# Rocket-Control5.net
KiCad netlist of a schematic drawn in EAGLE
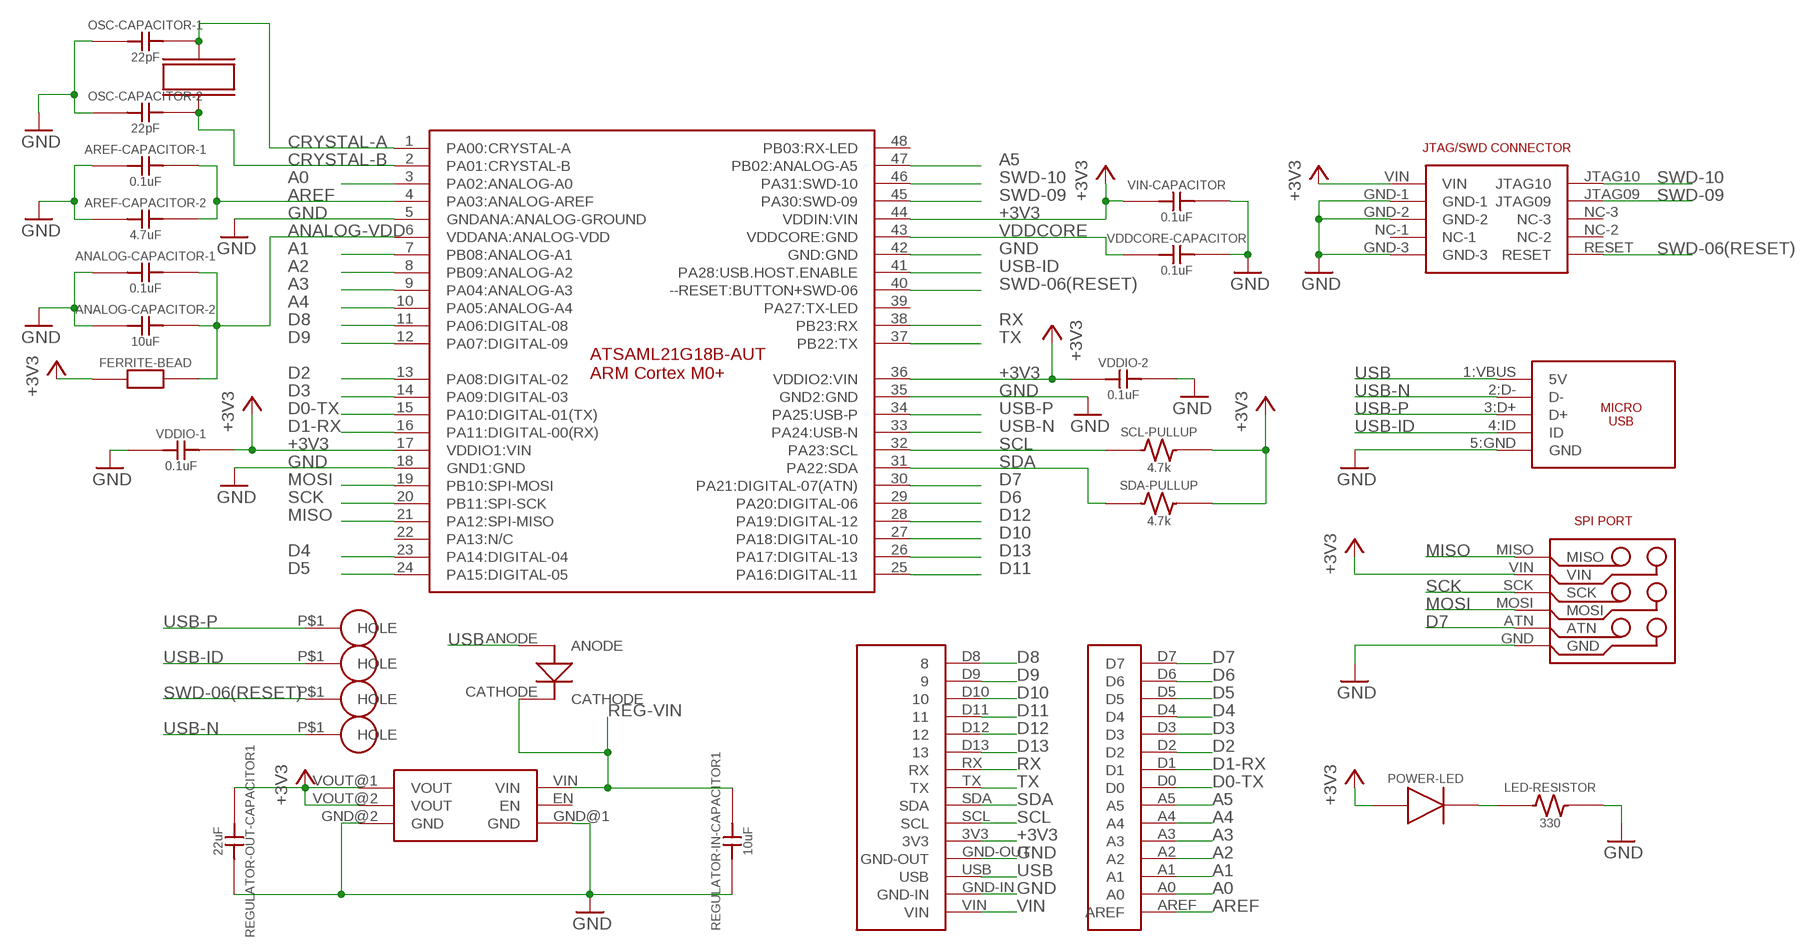
[diagram p0: schematic, sheet 1]

(export (version "E")
  (design (tool "Eeschema 10.0.6"))
  (components
    (comp (ref "ANALOG-CAPACITOR-1")
      (value "0.1uF")
      (footprint "eagle-import:C0402")
      (fields (field (name "MANF") "Samsung Electro-Mechanics America, Inc."))
      (libsource (lib "eagle-import") (part "CAPACITORC0402"))
    )
    (comp (ref "ANALOG-CAPACITOR-2")
      (value "10uF")
      (footprint "eagle-import:C0402")
      (fields (field (name "MANF") "Samsung Electro-Mechanics America, Inc."))
      (libsource (lib "eagle-import") (part "CAPACITORC0402"))
    )
    (comp (ref "AREF-CAPACITOR-1")
      (value "0.1uF")
      (footprint "eagle-import:C0402")
      (fields (field (name "MANF") "Samsung Electro-Mechanics America, Inc."))
      (libsource (lib "eagle-import") (part "CAPACITORC0402"))
    )
    (comp (ref "AREF-CAPACITOR-2")
      (value "4.7uF")
      (footprint "eagle-import:C0402")
      (fields (field (name "MANF") "Samsung Electro-Mechanics America, Inc."))
      (libsource (lib "eagle-import") (part "CAPACITORC0402"))
    )
    (comp (ref "ARM-CORTEX-MO+")
      (value "ATSAML21G18B-AUT")
      (footprint "eagle-import:TQFP48")
      (fields (field (name "MANF") "Microchip Technology"))
      (libsource (lib "eagle-import") (part "ATSAML21G18B-AUT"))
    )
    (comp (ref "FERRITE-BEAD")
      (value "BLM18PG471SN1D")
      (footprint "eagle-import:C0603")
      (fields (field (name "MANF") "Murata Electronics North America"))
      (libsource (lib "eagle-import") (part "BLM18PG471SN1D"))
    )
    (comp (ref "HEADER-SIDE-A")
      (value "HEADER-SIDE-A")
      (footprint "eagle-import:HEADER-SIDE-A")
      (libsource (lib "eagle-import") (part "HEADER-SIDE-A"))
    )
    (comp (ref "HEADER-SIDE-B")
      (value "HEADER-SIDE-B")
      (footprint "eagle-import:HEADER-SIDE-B")
      (fields (field (name "MANF") "Sullins Connector Solutions"))
      (libsource (lib "eagle-import") (part "HEADER-SIDE-B"))
    )
    (comp (ref "JTAG-CONNECTOR")
      (value "JTAG-MINI")
      (footprint "eagle-import:JTAG-MINI")
      (fields (field (name "MANF") "Amphenol FCI"))
      (libsource (lib "eagle-import") (part "JTAG-MINI"))
    )
    (comp (ref "LED-RESISTOR")
      (value "330")
      (footprint "eagle-import:C0603")
      (fields (field (name "MANF") "Samsung Electro-Mechanics America, Inc."))
      (libsource (lib "eagle-import") (part "RESISTORC0603"))
    )
    (comp (ref "MICRO-USB-CONNECTOR")
      (value "10118194-0001LF")
      (footprint "eagle-import:10118194-0001LF")
      (fields (field (name "MANF") "Amphenol FCI"))
      (libsource (lib "eagle-import") (part "10118194-0001LF"))
    )
    (comp (ref "OSC-CAPACITOR-1")
      (value "22pF")
      (footprint "eagle-import:C0603")
      (fields (field (name "MANF") "Samsung Electro-Mechanics America, Inc."))
      (libsource (lib "eagle-import") (part "CAPACITORC0603"))
    )
    (comp (ref "OSC-CAPACITOR-2")
      (value "22pF")
      (footprint "eagle-import:C0603")
      (fields (field (name "MANF") "Samsung Electro-Mechanics America, Inc."))
      (libsource (lib "eagle-import") (part "CAPACITORC0603"))
    )
    (comp (ref "POWER-LED")
      (value "APTD1608ZGC")
      (footprint "eagle-import:C0603")
      (fields (field (name "MANF") "Kingbright"))
      (libsource (lib "eagle-import") (part "APTD1608ZGC"))
    )
    (comp (ref "REGULATOR-IN-CAPACITOR1")
      (value "10uF")
      (footprint "eagle-import:C0402")
      (fields (field (name "MANF") "Samsung Electro-Mechanics America, Inc."))
      (libsource (lib "eagle-import") (part "CAPACITORC0402"))
    )
    (comp (ref "REGULATOR-OUT-CAPACITOR1")
      (value "22uF")
      (footprint "eagle-import:C0402")
      (fields (field (name "MANF") "Samsung Electro-Mechanics America, Inc."))
      (libsource (lib "eagle-import") (part "CAPACITORC0402"))
    )
    (comp (ref "SCL-PULLUP")
      (value "4.7k")
      (footprint "eagle-import:C0402")
      (fields (field (name "MANF") "Samsung Electro-Mechanics America, Inc."))
      (libsource (lib "eagle-import") (part "RESISTORC0402"))
    )
    (comp (ref "SDA-PULLUP")
      (value "4.7k")
      (footprint "eagle-import:C0402")
      (fields (field (name "MANF") "Samsung Electro-Mechanics America, Inc."))
      (libsource (lib "eagle-import") (part "RESISTORC0402"))
    )
    (comp (ref "SPI-PORT")
      (value "SPI-PORT")
      (footprint "eagle-import:SPI-PORT")
      (libsource (lib "eagle-import") (part "SPI-PORT"))
    )
    (comp (ref "U$1")
      (value "ABS07-32.768KHZ-T")
      (footprint "eagle-import:ABS07-32.768KHZ-T")
      (fields (field (name "MANF") "Abracon LLC"))
      (libsource (lib "eagle-import") (part "ABS07-32.768KHZ-T"))
    )
    (comp (ref "U$2")
      (value "MIC5528")
      (footprint "eagle-import:MIC5528")
      (fields (field (name "MANF") "Microchip Technology"))
      (libsource (lib "eagle-import") (part "MIC5528"))
    )
    (comp (ref "U$3")
      (value "DIODE-STANDARD")
      (footprint "eagle-import:DIODE-STANDARD")
      (fields (field (name "MANF") "Panasonic Electronic Components"))
      (libsource (lib "eagle-import") (part "DIODE-STANDARD"))
    )
    (comp (ref "U$4")
      (value "HEADER-HOLE")
      (footprint "eagle-import:HEADER-HOLE")
      (libsource (lib "eagle-import") (part "HEADER-HOLE"))
    )
    (comp (ref "U$5")
      (value "HEADER-HOLE")
      (footprint "eagle-import:HEADER-HOLE")
      (libsource (lib "eagle-import") (part "HEADER-HOLE"))
    )
    (comp (ref "U$6")
      (value "HEADER-HOLE")
      (footprint "eagle-import:HEADER-HOLE")
      (libsource (lib "eagle-import") (part "HEADER-HOLE"))
    )
    (comp (ref "U$7")
      (value "HEADER-HOLE")
      (footprint "eagle-import:HEADER-HOLE")
      (libsource (lib "eagle-import") (part "HEADER-HOLE"))
    )
    (comp (ref "VDDCORE-CAPACITOR")
      (value "0.1uF")
      (footprint "eagle-import:C0402")
      (fields (field (name "MANF") "Samsung Electro-Mechanics America, Inc."))
      (libsource (lib "eagle-import") (part "CAPACITORC0402"))
    )
    (comp (ref "VDDIO-1")
      (value "0.1uF")
      (footprint "eagle-import:C0402")
      (fields (field (name "MANF") "Samsung Electro-Mechanics America, Inc."))
      (libsource (lib "eagle-import") (part "CAPACITORC0402"))
    )
    (comp (ref "VDDIO-2")
      (value "0.1uF")
      (footprint "eagle-import:C0402")
      (fields (field (name "MANF") "Samsung Electro-Mechanics America, Inc."))
      (libsource (lib "eagle-import") (part "CAPACITORC0402"))
    )
    (comp (ref "VIN-CAPACITOR")
      (value "0.1uF")
      (footprint "eagle-import:C0402")
      (fields (field (name "MANF") "Samsung Electro-Mechanics America, Inc."))
      (libsource (lib "eagle-import") (part "CAPACITORC0402"))
    )
  )
  (nets
    (net (code "1") (name "+3V3") (class "Default")
      (node (ref "ARM-CORTEX-MO+") (pin "17") (pinfunction "VDDIO1:VIN_17") (pintype "bidirectional"))
      (node (ref "ARM-CORTEX-MO+") (pin "36") (pinfunction "VDDIO2:VIN_36") (pintype "bidirectional"))
      (node (ref "ARM-CORTEX-MO+") (pin "44") (pinfunction "VDDIN:VIN_44") (pintype "bidirectional"))
      (node (ref "FERRITE-BEAD") (pin "1") (pinfunction "P$1_1") (pintype "bidirectional"))
      (node (ref "HEADER-SIDE-B") (pin "3V3") (pinfunction "3V3_3V3") (pintype "bidirectional"))
      (node (ref "JTAG-CONNECTOR") (pin "VIN") (pinfunction "VIN_VIN") (pintype "bidirectional"))
      (node (ref "POWER-LED") (pin "1") (pinfunction "P$1_1") (pintype "bidirectional"))
      (node (ref "REGULATOR-OUT-CAPACITOR1") (pin "1") (pinfunction "A_1") (pintype "bidirectional"))
      (node (ref "SCL-PULLUP") (pin "2") (pinfunction "P$2_2") (pintype "bidirectional"))
      (node (ref "SDA-PULLUP") (pin "2") (pinfunction "P$2_2") (pintype "bidirectional"))
      (node (ref "SPI-PORT") (pin "VIN") (pinfunction "VIN_VIN") (pintype "bidirectional"))
      (node (ref "U$2") (pin "VOUT@1") (pinfunction "VOUT_VOUT@1") (pintype "bidirectional"))
      (node (ref "U$2") (pin "VOUT@2") (pinfunction "VOUT_VOUT@2") (pintype "bidirectional"))
      (node (ref "VDDIO-1") (pin "2") (pinfunction "B_2") (pintype "bidirectional"))
      (node (ref "VDDIO-2") (pin "2") (pinfunction "B_2") (pintype "bidirectional"))
      (node (ref "VIN-CAPACITOR") (pin "1") (pinfunction "A_1") (pintype "bidirectional"))
    )
    (net (code "2") (name "/A0") (class "Default")
      (node (ref "ARM-CORTEX-MO+") (pin "3") (pinfunction "PA02:ANALOG-A0_3") (pintype "bidirectional"))
      (node (ref "HEADER-SIDE-A") (pin "A0") (pinfunction "A0_A0") (pintype "bidirectional"))
    )
    (net (code "3") (name "/A1") (class "Default")
      (node (ref "ARM-CORTEX-MO+") (pin "7") (pinfunction "PB08:ANALOG-A1_7") (pintype "bidirectional"))
      (node (ref "HEADER-SIDE-A") (pin "A1") (pinfunction "A1_A1") (pintype "bidirectional"))
    )
    (net (code "4") (name "/A2") (class "Default")
      (node (ref "ARM-CORTEX-MO+") (pin "8") (pinfunction "PB09:ANALOG-A2_8") (pintype "bidirectional"))
      (node (ref "HEADER-SIDE-A") (pin "A2") (pinfunction "A2_A2") (pintype "bidirectional"))
    )
    (net (code "5") (name "/A3") (class "Default")
      (node (ref "ARM-CORTEX-MO+") (pin "9") (pinfunction "PA04:ANALOG-A3_9") (pintype "bidirectional"))
      (node (ref "HEADER-SIDE-A") (pin "A3") (pinfunction "A3_A3") (pintype "bidirectional"))
    )
    (net (code "6") (name "/A4") (class "Default")
      (node (ref "ARM-CORTEX-MO+") (pin "10") (pinfunction "PA05:ANALOG-A4_10") (pintype "bidirectional"))
      (node (ref "HEADER-SIDE-A") (pin "A4") (pinfunction "A4_A4") (pintype "bidirectional"))
    )
    (net (code "7") (name "/A5") (class "Default")
      (node (ref "ARM-CORTEX-MO+") (pin "47") (pinfunction "PB02:ANALOG-A5_47") (pintype "bidirectional"))
      (node (ref "HEADER-SIDE-A") (pin "A5") (pinfunction "A5_A5") (pintype "bidirectional"))
    )
    (net (code "8") (name "/ANALOG-VDD") (class "Default")
      (node (ref "ANALOG-CAPACITOR-1") (pin "2") (pinfunction "B_2") (pintype "bidirectional"))
      (node (ref "ANALOG-CAPACITOR-2") (pin "2") (pinfunction "B_2") (pintype "bidirectional"))
      (node (ref "ARM-CORTEX-MO+") (pin "6") (pinfunction "VDDANA:ANALOG-VDD_6") (pintype "bidirectional"))
      (node (ref "FERRITE-BEAD") (pin "2") (pinfunction "P$2_2") (pintype "bidirectional"))
    )
    (net (code "9") (name "/AREF") (class "Default")
      (node (ref "AREF-CAPACITOR-1") (pin "2") (pinfunction "B_2") (pintype "bidirectional"))
      (node (ref "AREF-CAPACITOR-2") (pin "2") (pinfunction "B_2") (pintype "bidirectional"))
      (node (ref "ARM-CORTEX-MO+") (pin "4") (pinfunction "PA03:ANALOG-AREF_4") (pintype "bidirectional"))
      (node (ref "HEADER-SIDE-A") (pin "AREF") (pinfunction "AREF_AREF") (pintype "bidirectional"))
    )
    (net (code "10") (name "/CRYSTAL-A") (class "Default")
      (node (ref "ARM-CORTEX-MO+") (pin "1") (pinfunction "PA00:CRYSTAL-A_1") (pintype "bidirectional"))
      (node (ref "OSC-CAPACITOR-1") (pin "2") (pinfunction "B_2") (pintype "bidirectional"))
      (node (ref "U$1") (pin "P$2") (pinfunction "P$2_P$2") (pintype "bidirectional"))
    )
    (net (code "11") (name "/CRYSTAL-B") (class "Default")
      (node (ref "ARM-CORTEX-MO+") (pin "2") (pinfunction "PA01:CRYSTAL-B_2") (pintype "bidirectional"))
      (node (ref "OSC-CAPACITOR-2") (pin "2") (pinfunction "B_2") (pintype "bidirectional"))
      (node (ref "U$1") (pin "P$1") (pinfunction "P$1_P$1") (pintype "bidirectional"))
    )
    (net (code "12") (name "/D0-TX") (class "Default")
      (node (ref "ARM-CORTEX-MO+") (pin "15") (pinfunction "PA10:DIGITAL-01(TX)_15") (pintype "bidirectional"))
      (node (ref "HEADER-SIDE-A") (pin "D0") (pinfunction "D0_D0") (pintype "bidirectional"))
    )
    (net (code "13") (name "/D1-RX") (class "Default")
      (node (ref "ARM-CORTEX-MO+") (pin "16") (pinfunction "PA11:DIGITAL-00(RX)_16") (pintype "bidirectional"))
      (node (ref "HEADER-SIDE-A") (pin "D1") (pinfunction "D1_D1") (pintype "bidirectional"))
    )
    (net (code "14") (name "/D2") (class "Default")
      (node (ref "ARM-CORTEX-MO+") (pin "13") (pinfunction "PA08:DIGITAL-02_13") (pintype "bidirectional"))
      (node (ref "HEADER-SIDE-A") (pin "D2") (pinfunction "D2_D2") (pintype "bidirectional"))
    )
    (net (code "15") (name "/D3") (class "Default")
      (node (ref "ARM-CORTEX-MO+") (pin "14") (pinfunction "PA09:DIGITAL-03_14") (pintype "bidirectional"))
      (node (ref "HEADER-SIDE-A") (pin "D3") (pinfunction "D3_D3") (pintype "bidirectional"))
    )
    (net (code "16") (name "/D4") (class "Default")
      (node (ref "ARM-CORTEX-MO+") (pin "23") (pinfunction "PA14:DIGITAL-04_23") (pintype "bidirectional"))
      (node (ref "HEADER-SIDE-A") (pin "D4") (pinfunction "D4_D4") (pintype "bidirectional"))
    )
    (net (code "17") (name "/D5") (class "Default")
      (node (ref "ARM-CORTEX-MO+") (pin "24") (pinfunction "PA15:DIGITAL-05_24") (pintype "bidirectional"))
      (node (ref "HEADER-SIDE-A") (pin "D5") (pinfunction "D5_D5") (pintype "bidirectional"))
    )
    (net (code "18") (name "/D6") (class "Default")
      (node (ref "ARM-CORTEX-MO+") (pin "29") (pinfunction "PA20:DIGITAL-06_29") (pintype "bidirectional"))
      (node (ref "HEADER-SIDE-A") (pin "D6") (pinfunction "D6_D6") (pintype "bidirectional"))
    )
    (net (code "19") (name "/D7") (class "Default")
      (node (ref "ARM-CORTEX-MO+") (pin "30") (pinfunction "PA21:DIGITAL-07(ATN)_30") (pintype "bidirectional"))
      (node (ref "HEADER-SIDE-A") (pin "D7") (pinfunction "D7_D7") (pintype "bidirectional"))
      (node (ref "SPI-PORT") (pin "ATN") (pinfunction "ATN_ATN") (pintype "bidirectional"))
    )
    (net (code "20") (name "/D8") (class "Default")
      (node (ref "ARM-CORTEX-MO+") (pin "11") (pinfunction "PA06:DIGITAL-08_11") (pintype "bidirectional"))
      (node (ref "HEADER-SIDE-B") (pin "D8") (pinfunction "8_D8") (pintype "bidirectional"))
    )
    (net (code "21") (name "/D9") (class "Default")
      (node (ref "ARM-CORTEX-MO+") (pin "12") (pinfunction "PA07:DIGITAL-09_12") (pintype "bidirectional"))
      (node (ref "HEADER-SIDE-B") (pin "D9") (pinfunction "9_D9") (pintype "bidirectional"))
    )
    (net (code "22") (name "/D10") (class "Default")
      (node (ref "ARM-CORTEX-MO+") (pin "27") (pinfunction "PA18:DIGITAL-10_27") (pintype "bidirectional"))
      (node (ref "HEADER-SIDE-B") (pin "D10") (pinfunction "10_D10") (pintype "bidirectional"))
    )
    (net (code "23") (name "/D11") (class "Default")
      (node (ref "ARM-CORTEX-MO+") (pin "25") (pinfunction "PA16:DIGITAL-11_25") (pintype "bidirectional"))
      (node (ref "HEADER-SIDE-B") (pin "D11") (pinfunction "11_D11") (pintype "bidirectional"))
    )
    (net (code "24") (name "/D12") (class "Default")
      (node (ref "ARM-CORTEX-MO+") (pin "28") (pinfunction "PA19:DIGITAL-12_28") (pintype "bidirectional"))
      (node (ref "HEADER-SIDE-B") (pin "D12") (pinfunction "12_D12") (pintype "bidirectional"))
    )
    (net (code "25") (name "/D13") (class "Default")
      (node (ref "ARM-CORTEX-MO+") (pin "26") (pinfunction "PA17:DIGITAL-13_26") (pintype "bidirectional"))
      (node (ref "HEADER-SIDE-B") (pin "D13") (pinfunction "13_D13") (pintype "bidirectional"))
    )
    (net (code "26") (name "/MISO") (class "Default")
      (node (ref "ARM-CORTEX-MO+") (pin "21") (pinfunction "PA12:SPI-MISO_21") (pintype "bidirectional"))
      (node (ref "SPI-PORT") (pin "MISO") (pinfunction "MISO_MISO") (pintype "bidirectional"))
    )
    (net (code "27") (name "/MOSI") (class "Default")
      (node (ref "ARM-CORTEX-MO+") (pin "19") (pinfunction "PB10:SPI-MOSI_19") (pintype "bidirectional"))
      (node (ref "SPI-PORT") (pin "MOSI") (pinfunction "MOSI_MOSI") (pintype "bidirectional"))
    )
    (net (code "28") (name "/REG-VIN") (class "Default")
      (node (ref "REGULATOR-IN-CAPACITOR1") (pin "2") (pinfunction "B_2") (pintype "bidirectional"))
      (node (ref "U$2") (pin "VIN") (pinfunction "VIN_VIN") (pintype "bidirectional"))
      (node (ref "U$3") (pin "CATHODE") (pinfunction "CATHODE_CATHODE") (pintype "bidirectional"))
    )
    (net (code "29") (name "/RX") (class "Default")
      (node (ref "ARM-CORTEX-MO+") (pin "38") (pinfunction "PB23:RX_38") (pintype "bidirectional"))
      (node (ref "HEADER-SIDE-B") (pin "RX") (pinfunction "RX_RX") (pintype "bidirectional"))
    )
    (net (code "30") (name "/SCK") (class "Default")
      (node (ref "ARM-CORTEX-MO+") (pin "20") (pinfunction "PB11:SPI-SCK_20") (pintype "bidirectional"))
      (node (ref "SPI-PORT") (pin "SCK") (pinfunction "SCK_SCK") (pintype "bidirectional"))
    )
    (net (code "31") (name "/SCL") (class "Default")
      (node (ref "ARM-CORTEX-MO+") (pin "32") (pinfunction "PA23:SCL_32") (pintype "bidirectional"))
      (node (ref "HEADER-SIDE-B") (pin "SCL") (pinfunction "SCL_SCL") (pintype "bidirectional"))
      (node (ref "SCL-PULLUP") (pin "1") (pinfunction "P$1_1") (pintype "bidirectional"))
    )
    (net (code "32") (name "/SDA") (class "Default")
      (node (ref "ARM-CORTEX-MO+") (pin "31") (pinfunction "PA22:SDA_31") (pintype "bidirectional"))
      (node (ref "HEADER-SIDE-B") (pin "SDA") (pinfunction "SDA_SDA") (pintype "bidirectional"))
      (node (ref "SDA-PULLUP") (pin "1") (pinfunction "P$1_1") (pintype "bidirectional"))
    )
    (net (code "33") (name "/SWD-06(RESET)") (class "Default")
      (node (ref "ARM-CORTEX-MO+") (pin "40") (pinfunction "--RESET:BUTTON+SWD-06_40") (pintype "bidirectional"))
      (node (ref "JTAG-CONNECTOR") (pin "RESET") (pinfunction "RESET_RESET") (pintype "bidirectional"))
      (node (ref "U$5") (pin "P$1") (pinfunction "HOLE_P$1") (pintype "bidirectional"))
    )
    (net (code "34") (name "/SWD-09") (class "Default")
      (node (ref "ARM-CORTEX-MO+") (pin "45") (pinfunction "PA30:SWD-09_45") (pintype "bidirectional"))
      (node (ref "JTAG-CONNECTOR") (pin "JTAG09") (pinfunction "JTAG09_JTAG09") (pintype "bidirectional"))
    )
    (net (code "35") (name "/SWD-10") (class "Default")
      (node (ref "ARM-CORTEX-MO+") (pin "46") (pinfunction "PA31:SWD-10_46") (pintype "bidirectional"))
      (node (ref "JTAG-CONNECTOR") (pin "JTAG10") (pinfunction "JTAG10_JTAG10") (pintype "bidirectional"))
    )
    (net (code "36") (name "/TX") (class "Default")
      (node (ref "ARM-CORTEX-MO+") (pin "37") (pinfunction "PB22:TX_37") (pintype "bidirectional"))
      (node (ref "HEADER-SIDE-B") (pin "TX") (pinfunction "TX_TX") (pintype "bidirectional"))
    )
    (net (code "37") (name "/USB") (class "Default")
      (node (ref "HEADER-SIDE-B") (pin "USB") (pinfunction "USB_USB") (pintype "bidirectional"))
      (node (ref "MICRO-USB-CONNECTOR") (pin "1:VBUS") (pinfunction "5V_1:VBUS") (pintype "bidirectional"))
      (node (ref "U$3") (pin "ANODE") (pinfunction "ANODE_ANODE") (pintype "bidirectional"))
    )
    (net (code "38") (name "/USB-ID") (class "Default")
      (node (ref "ARM-CORTEX-MO+") (pin "41") (pinfunction "PA28:USB.HOST.ENABLE_41") (pintype "bidirectional"))
      (node (ref "MICRO-USB-CONNECTOR") (pin "4:ID") (pinfunction "ID_4:ID") (pintype "bidirectional"))
      (node (ref "U$4") (pin "P$1") (pinfunction "HOLE_P$1") (pintype "bidirectional"))
    )
    (net (code "39") (name "/USB-N") (class "Default")
      (node (ref "ARM-CORTEX-MO+") (pin "33") (pinfunction "PA24:USB-N_33") (pintype "bidirectional"))
      (node (ref "MICRO-USB-CONNECTOR") (pin "2:D-") (pinfunction "D-_2:D-") (pintype "bidirectional"))
      (node (ref "U$6") (pin "P$1") (pinfunction "HOLE_P$1") (pintype "bidirectional"))
    )
    (net (code "40") (name "/USB-P") (class "Default")
      (node (ref "ARM-CORTEX-MO+") (pin "34") (pinfunction "PA25:USB-P_34") (pintype "bidirectional"))
      (node (ref "MICRO-USB-CONNECTOR") (pin "3:D+") (pinfunction "D+_3:D+") (pintype "bidirectional"))
      (node (ref "U$7") (pin "P$1") (pinfunction "HOLE_P$1") (pintype "bidirectional"))
    )
    (net (code "41") (name "/VDDCORE") (class "Default")
      (node (ref "ARM-CORTEX-MO+") (pin "43") (pinfunction "VDDCORE:GND_43") (pintype "bidirectional"))
      (node (ref "VDDCORE-CAPACITOR") (pin "1") (pinfunction "A_1") (pintype "bidirectional"))
    )
    (net (code "42") (name "/VIN") (class "Default")
      (node (ref "HEADER-SIDE-B") (pin "VIN") (pinfunction "VIN_VIN") (pintype "bidirectional"))
    )
    (net (code "43") (name "GND") (class "Default")
      (node (ref "ANALOG-CAPACITOR-1") (pin "1") (pinfunction "A_1") (pintype "bidirectional"))
      (node (ref "ANALOG-CAPACITOR-2") (pin "1") (pinfunction "A_1") (pintype "bidirectional"))
      (node (ref "AREF-CAPACITOR-1") (pin "1") (pinfunction "A_1") (pintype "bidirectional"))
      (node (ref "AREF-CAPACITOR-2") (pin "1") (pinfunction "A_1") (pintype "bidirectional"))
      (node (ref "ARM-CORTEX-MO+") (pin "18") (pinfunction "GND1:GND_18") (pintype "bidirectional"))
      (node (ref "ARM-CORTEX-MO+") (pin "35") (pinfunction "GND2:GND_35") (pintype "bidirectional"))
      (node (ref "ARM-CORTEX-MO+") (pin "42") (pinfunction "GND:GND_42") (pintype "bidirectional"))
      (node (ref "ARM-CORTEX-MO+") (pin "5") (pinfunction "GNDANA:ANALOG-GROUND_5") (pintype "bidirectional"))
      (node (ref "HEADER-SIDE-B") (pin "GND-IN") (pinfunction "GND-IN_GND-IN") (pintype "bidirectional"))
      (node (ref "HEADER-SIDE-B") (pin "GND-OUT") (pinfunction "GND-OUT_GND-OUT") (pintype "bidirectional"))
      (node (ref "JTAG-CONNECTOR") (pin "GND-1") (pinfunction "GND-1_GND-1") (pintype "bidirectional"))
      (node (ref "JTAG-CONNECTOR") (pin "GND-2") (pinfunction "GND-2_GND-2") (pintype "bidirectional"))
      (node (ref "JTAG-CONNECTOR") (pin "GND-3") (pinfunction "GND-3_GND-3") (pintype "bidirectional"))
      (node (ref "LED-RESISTOR") (pin "2") (pinfunction "P$2_2") (pintype "bidirectional"))
      (node (ref "MICRO-USB-CONNECTOR") (pin "5:GND") (pinfunction "GND_5:GND") (pintype "bidirectional"))
      (node (ref "OSC-CAPACITOR-1") (pin "1") (pinfunction "A_1") (pintype "bidirectional"))
      (node (ref "OSC-CAPACITOR-2") (pin "1") (pinfunction "A_1") (pintype "bidirectional"))
      (node (ref "REGULATOR-IN-CAPACITOR1") (pin "1") (pinfunction "A_1") (pintype "bidirectional"))
      (node (ref "REGULATOR-OUT-CAPACITOR1") (pin "2") (pinfunction "B_2") (pintype "bidirectional"))
      (node (ref "SPI-PORT") (pin "GND") (pinfunction "GND_GND") (pintype "bidirectional"))
      (node (ref "U$2") (pin "GND@1") (pinfunction "GND_GND@1") (pintype "bidirectional"))
      (node (ref "U$2") (pin "GND@2") (pinfunction "GND_GND@2") (pintype "bidirectional"))
      (node (ref "VDDCORE-CAPACITOR") (pin "2") (pinfunction "B_2") (pintype "bidirectional"))
      (node (ref "VDDIO-1") (pin "1") (pinfunction "A_1") (pintype "bidirectional"))
      (node (ref "VDDIO-2") (pin "1") (pinfunction "A_1") (pintype "bidirectional"))
      (node (ref "VIN-CAPACITOR") (pin "2") (pinfunction "B_2") (pintype "bidirectional"))
    )
    (net (code "44") (name "Net-(LED-RESISTOR-P$1)") (class "Default")
      (node (ref "LED-RESISTOR") (pin "1") (pinfunction "P$1_1") (pintype "bidirectional"))
      (node (ref "POWER-LED") (pin "2") (pinfunction "P$2_2") (pintype "bidirectional"))
    )
    (net (code "45") (name "unconnected-(ARM-CORTEX-MO+-PA13:N{slash}C-Pad22)") (class "Default")
      (node (ref "ARM-CORTEX-MO+") (pin "22") (pinfunction "PA13:N/C_22") (pintype "bidirectional"))
    )
    (net (code "46") (name "unconnected-(ARM-CORTEX-MO+-PA27:TX-LED-Pad39)") (class "Default")
      (node (ref "ARM-CORTEX-MO+") (pin "39") (pinfunction "PA27:TX-LED_39") (pintype "bidirectional"))
    )
    (net (code "47") (name "unconnected-(ARM-CORTEX-MO+-PB03:RX-LED-Pad48)") (class "Default")
      (node (ref "ARM-CORTEX-MO+") (pin "48") (pinfunction "PB03:RX-LED_48") (pintype "bidirectional"))
    )
    (net (code "48") (name "unconnected-(JTAG-CONNECTOR-PadNC-1)") (class "Default")
      (node (ref "JTAG-CONNECTOR") (pin "NC-1") (pinfunction "NC-1_NC-1") (pintype "bidirectional"))
    )
    (net (code "49") (name "unconnected-(JTAG-CONNECTOR-PadNC-2)") (class "Default")
      (node (ref "JTAG-CONNECTOR") (pin "NC-2") (pinfunction "NC-2_NC-2") (pintype "bidirectional"))
    )
    (net (code "50") (name "unconnected-(JTAG-CONNECTOR-PadNC-3)") (class "Default")
      (node (ref "JTAG-CONNECTOR") (pin "NC-3") (pinfunction "NC-3_NC-3") (pintype "bidirectional"))
    )
    (net (code "51") (name "unconnected-(U$2-PadEN)") (class "Default")
      (node (ref "U$2") (pin "EN") (pinfunction "EN_EN") (pintype "bidirectional"))
    )
  )
)
